# Driver.net
KiCad netlist of a schematic drawn in Altium Designer
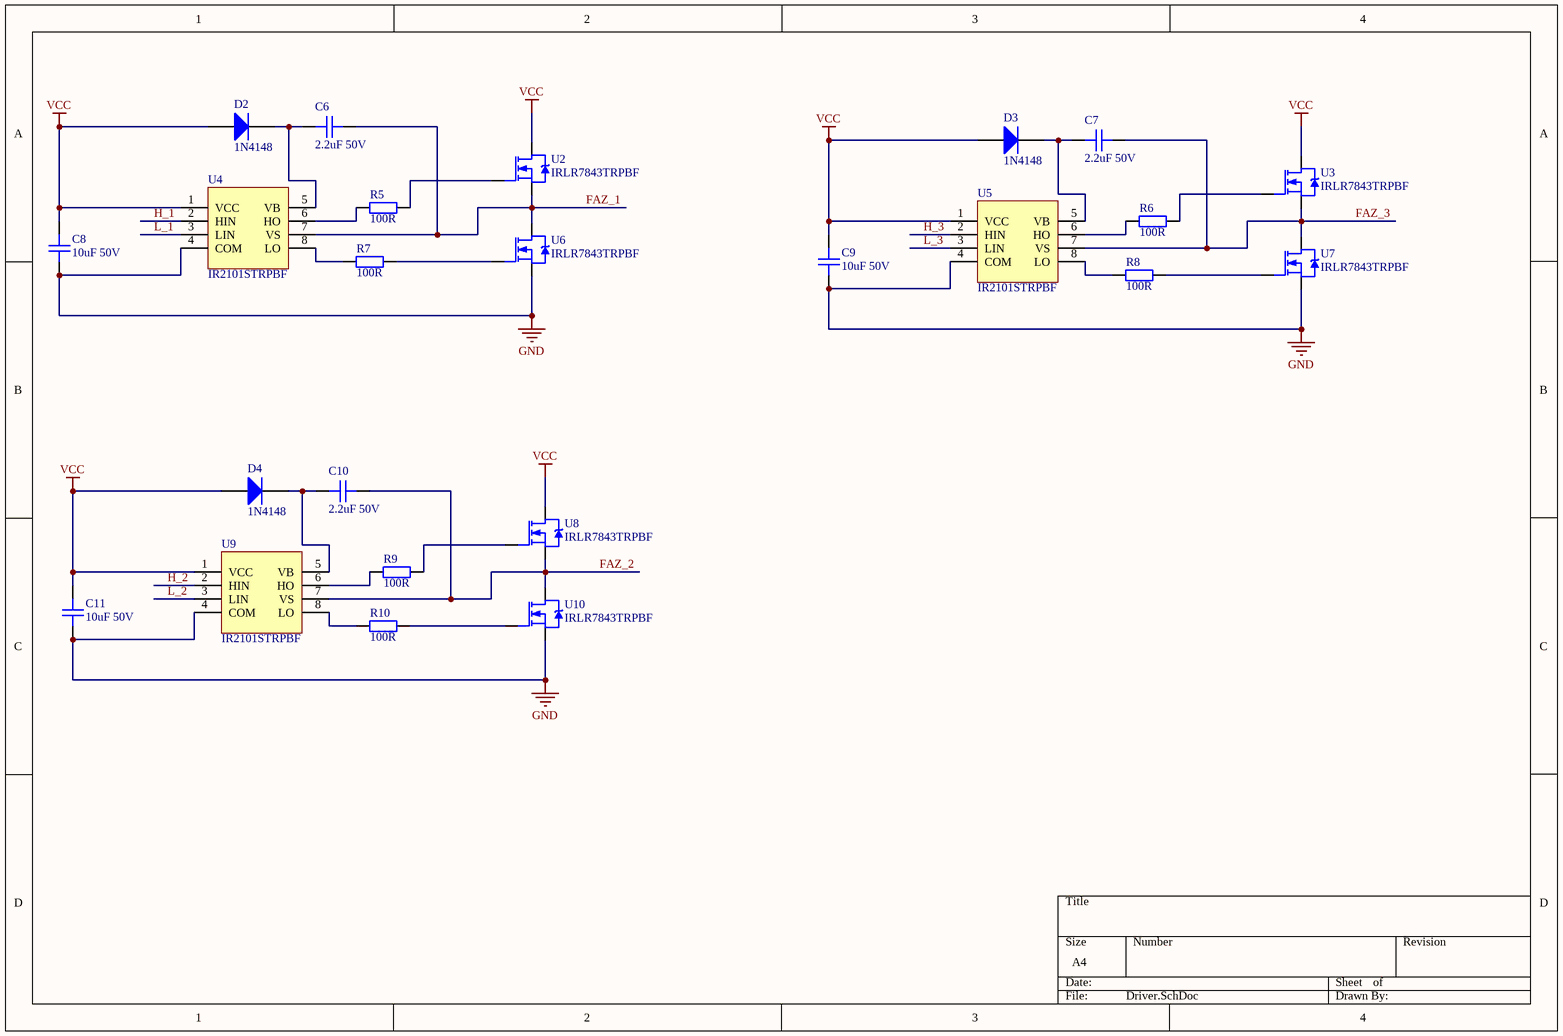
[diagram p0: Driver.SchDoc]

(export (version "E")
  (design (tool "Eeschema 10.0.6"))
  (components
    (comp (ref "C6")
      (value "CAP CER 2.2UF 50V X5R 1206")
      (footprint "CAP 1206/3216")
      (description "2.2µF ±10% 50V Ceramic Capacitor X5R 1206 (3216 Metric)")
      (fields (field (name "DEGER") "2.2uF 50V"))
      (libsource (lib "ESC") (part "2.2uF 50V 1206"))
    )
    (comp (ref "C7")
      (value "CAP CER 2.2UF 50V X5R 1206")
      (footprint "CAP 1206/3216")
      (description "2.2µF ±10% 50V Ceramic Capacitor X5R 1206 (3216 Metric)")
      (fields (field (name "DEGER") "2.2uF 50V"))
      (libsource (lib "ESC") (part "2.2uF 50V 1206"))
    )
    (comp (ref "C8")
      (value "CAP CER 10UF 50V X5R 1206")
      (footprint "CAP 1206/3216")
      (description "10µF ±10% 50V Ceramic Capacitor X5R 1206 (3216 Metric)")
      (fields (field (name "DEGER") "10uF 50V"))
      (libsource (lib "ESC") (part "10uF 50V 1206"))
    )
    (comp (ref "C9")
      (value "CAP CER 10UF 50V X5R 1206")
      (footprint "CAP 1206/3216")
      (description "10µF ±10% 50V Ceramic Capacitor X5R 1206 (3216 Metric)")
      (fields (field (name "DEGER") "10uF 50V"))
      (libsource (lib "ESC") (part "10uF 50V 1206"))
    )
    (comp (ref "C10")
      (value "CAP CER 2.2UF 50V X5R 1206")
      (footprint "CAP 1206/3216")
      (description "2.2µF ±10% 50V Ceramic Capacitor X5R 1206 (3216 Metric)")
      (fields (field (name "DEGER") "2.2uF 50V"))
      (libsource (lib "ESC") (part "2.2uF 50V 1206"))
    )
    (comp (ref "C11")
      (value "CAP CER 10UF 50V X5R 1206")
      (footprint "CAP 1206/3216")
      (description "10µF ±10% 50V Ceramic Capacitor X5R 1206 (3216 Metric)")
      (fields (field (name "DEGER") "10uF 50V"))
      (libsource (lib "ESC") (part "10uF 50V 1206"))
    )
    (comp (ref "D2")
      (value "1N4148 Diyot")
      (footprint "SOD-123")
      (description "DIODE GEN PURP 100V 150MA SOD123")
      (fields (field (name "DEGER") "1N4148"))
      (libsource (lib "ESC") (part "1N4148"))
    )
    (comp (ref "D3")
      (value "1N4148 Diyot")
      (footprint "SOD-123")
      (description "DIODE GEN PURP 100V 150MA SOD123")
      (fields (field (name "DEGER") "1N4148"))
      (libsource (lib "ESC") (part "1N4148"))
    )
    (comp (ref "D4")
      (value "1N4148 Diyot")
      (footprint "SOD-123")
      (description "DIODE GEN PURP 100V 150MA SOD123")
      (fields (field (name "DEGER") "1N4148"))
      (libsource (lib "ESC") (part "1N4148"))
    )
    (comp (ref "R5")
      (value "RES SMD 100 OHM 1% 1/8W 0805")
      (footprint "RES-0805")
      (description "100 Ohms ±1% 0.125W, 1/8W Chip Resistor 0805 (2012 Metric) Moisture Resistant Thick Film")
      (fields (field (name "DEGER") "100R"))
      (libsource (lib "ESC") (part "100R 0805"))
    )
    (comp (ref "R6")
      (value "RES SMD 100 OHM 1% 1/8W 0805")
      (footprint "RES-0805")
      (description "100 Ohms ±1% 0.125W, 1/8W Chip Resistor 0805 (2012 Metric) Moisture Resistant Thick Film")
      (fields (field (name "DEGER") "100R"))
      (libsource (lib "ESC") (part "100R 0805"))
    )
    (comp (ref "R7")
      (value "RES SMD 100 OHM 1% 1/8W 0805")
      (footprint "RES-0805")
      (description "100 Ohms ±1% 0.125W, 1/8W Chip Resistor 0805 (2012 Metric) Moisture Resistant Thick Film")
      (fields (field (name "DEGER") "100R"))
      (libsource (lib "ESC") (part "100R 0805"))
    )
    (comp (ref "R8")
      (value "RES SMD 100 OHM 1% 1/8W 0805")
      (footprint "RES-0805")
      (description "100 Ohms ±1% 0.125W, 1/8W Chip Resistor 0805 (2012 Metric) Moisture Resistant Thick Film")
      (fields (field (name "DEGER") "100R"))
      (libsource (lib "ESC") (part "100R 0805"))
    )
    (comp (ref "R9")
      (value "RES SMD 100 OHM 1% 1/8W 0805")
      (footprint "RES-0805")
      (description "100 Ohms ±1% 0.125W, 1/8W Chip Resistor 0805 (2012 Metric) Moisture Resistant Thick Film")
      (fields (field (name "DEGER") "100R"))
      (libsource (lib "ESC") (part "100R 0805"))
    )
    (comp (ref "R10")
      (value "RES SMD 100 OHM 1% 1/8W 0805")
      (footprint "RES-0805")
      (description "100 Ohms ±1% 0.125W, 1/8W Chip Resistor 0805 (2012 Metric) Moisture Resistant Thick Film")
      (fields (field (name "DEGER") "100R"))
      (libsource (lib "ESC") (part "100R 0805"))
    )
    (comp (ref "U2")
      (value "MOSFET N-CH 30V 161A DPAK")
      (footprint "DPAK")
      (description "N-Channel 30V 161A (Tc) 140W (Tc) Surface Mount D-Pak")
      (fields (field (name "DEGER") "IRLR7843TRPBF"))
      (libsource (lib "ESC_Project") (part "IRLR7843"))
    )
    (comp (ref "U3")
      (value "MOSFET N-CH 30V 161A DPAK")
      (footprint "DPAK")
      (description "N-Channel 30V 161A (Tc) 140W (Tc) Surface Mount D-Pak")
      (fields (field (name "DEGER") "IRLR7843TRPBF"))
      (libsource (lib "ESC_Project") (part "IRLR7843"))
    )
    (comp (ref "U4")
      (value "IC GATE DRVR HALF-BRIDGE 8SOIC")
      (footprint "SOIC8")
      (description "Half-Bridge Gate Driver IC Non-Inverting 8-SOIC")
      (fields (field (name "DEGER") "IR2101STRPBF"))
      (libsource (lib "ESC") (part "IR2101"))
    )
    (comp (ref "U5")
      (value "IC GATE DRVR HALF-BRIDGE 8SOIC")
      (footprint "SOIC8")
      (description "Half-Bridge Gate Driver IC Non-Inverting 8-SOIC")
      (fields (field (name "DEGER") "IR2101STRPBF"))
      (libsource (lib "ESC") (part "IR2101"))
    )
    (comp (ref "U6")
      (value "MOSFET N-CH 30V 161A DPAK")
      (footprint "DPAK")
      (description "N-Channel 30V 161A (Tc) 140W (Tc) Surface Mount D-Pak")
      (fields (field (name "DEGER") "IRLR7843TRPBF"))
      (libsource (lib "ESC_Project") (part "IRLR7843"))
    )
    (comp (ref "U7")
      (value "MOSFET N-CH 30V 161A DPAK")
      (footprint "DPAK")
      (description "N-Channel 30V 161A (Tc) 140W (Tc) Surface Mount D-Pak")
      (fields (field (name "DEGER") "IRLR7843TRPBF"))
      (libsource (lib "ESC_Project") (part "IRLR7843"))
    )
    (comp (ref "U8")
      (value "MOSFET N-CH 30V 161A DPAK")
      (footprint "DPAK")
      (description "N-Channel 30V 161A (Tc) 140W (Tc) Surface Mount D-Pak")
      (fields (field (name "DEGER") "IRLR7843TRPBF"))
      (libsource (lib "ESC_Project") (part "IRLR7843"))
    )
    (comp (ref "U9")
      (value "IC GATE DRVR HALF-BRIDGE 8SOIC")
      (footprint "SOIC8")
      (description "Half-Bridge Gate Driver IC Non-Inverting 8-SOIC")
      (fields (field (name "DEGER") "IR2101STRPBF"))
      (libsource (lib "ESC") (part "IR2101"))
    )
    (comp (ref "U10")
      (value "MOSFET N-CH 30V 161A DPAK")
      (footprint "DPAK")
      (description "N-Channel 30V 161A (Tc) 140W (Tc) Surface Mount D-Pak")
      (fields (field (name "DEGER") "IRLR7843TRPBF"))
      (libsource (lib "ESC_Project") (part "IRLR7843"))
    )
  )
  (nets
    (net (code "1") (name "/FAZ_1") (class "Default")
      (node (ref "C6") (pin "2") (pinfunction "2_2") (pintype "passive"))
      (node (ref "U2") (pin "3") (pinfunction "S_3") (pintype "passive"))
      (node (ref "U4") (pin "7") (pinfunction "VS_7") (pintype "passive"))
      (node (ref "U6") (pin "4") (pinfunction "D_4") (pintype "passive"))
    )
    (net (code "2") (name "/FAZ_2") (class "Default")
      (node (ref "C10") (pin "2") (pinfunction "2_2") (pintype "passive"))
      (node (ref "U10") (pin "4") (pinfunction "D_4") (pintype "passive"))
      (node (ref "U8") (pin "3") (pinfunction "S_3") (pintype "passive"))
      (node (ref "U9") (pin "7") (pinfunction "VS_7") (pintype "passive"))
    )
    (net (code "3") (name "/FAZ_3") (class "Default")
      (node (ref "C7") (pin "2") (pinfunction "2_2") (pintype "passive"))
      (node (ref "U3") (pin "3") (pinfunction "S_3") (pintype "passive"))
      (node (ref "U5") (pin "7") (pinfunction "VS_7") (pintype "passive"))
      (node (ref "U7") (pin "4") (pinfunction "D_4") (pintype "passive"))
    )
    (net (code "4") (name "/H_1") (class "Default")
      (node (ref "U4") (pin "2") (pinfunction "HIN_2") (pintype "passive"))
    )
    (net (code "5") (name "/H_2") (class "Default")
      (node (ref "U9") (pin "2") (pinfunction "HIN_2") (pintype "passive"))
    )
    (net (code "6") (name "/H_3") (class "Default")
      (node (ref "U5") (pin "2") (pinfunction "HIN_2") (pintype "passive"))
    )
    (net (code "7") (name "/L_1") (class "Default")
      (node (ref "U4") (pin "3") (pinfunction "LIN_3") (pintype "passive"))
    )
    (net (code "8") (name "/L_2") (class "Default")
      (node (ref "U9") (pin "3") (pinfunction "LIN_3") (pintype "passive"))
    )
    (net (code "9") (name "/L_3") (class "Default")
      (node (ref "U5") (pin "3") (pinfunction "LIN_3") (pintype "passive"))
    )
    (net (code "10") (name "GND") (class "Default")
      (node (ref "C11") (pin "1") (pinfunction "1_1") (pintype "passive"))
      (node (ref "C8") (pin "1") (pinfunction "1_1") (pintype "passive"))
      (node (ref "C9") (pin "1") (pinfunction "1_1") (pintype "passive"))
      (node (ref "U10") (pin "3") (pinfunction "S_3") (pintype "passive"))
      (node (ref "U4") (pin "4") (pinfunction "COM_4") (pintype "passive"))
      (node (ref "U5") (pin "4") (pinfunction "COM_4") (pintype "passive"))
      (node (ref "U6") (pin "3") (pinfunction "S_3") (pintype "passive"))
      (node (ref "U7") (pin "3") (pinfunction "S_3") (pintype "passive"))
      (node (ref "U9") (pin "4") (pinfunction "COM_4") (pintype "passive"))
    )
    (net (code "11") (name "Net-(D2-K)") (class "Default")
      (node (ref "C6") (pin "1") (pinfunction "1_1") (pintype "passive"))
      (node (ref "D2") (pin "2") (pinfunction "K_2") (pintype "passive"))
      (node (ref "U4") (pin "5") (pinfunction "VB_5") (pintype "passive"))
    )
    (net (code "12") (name "Net-(D3-K)") (class "Default")
      (node (ref "C7") (pin "1") (pinfunction "1_1") (pintype "passive"))
      (node (ref "D3") (pin "2") (pinfunction "K_2") (pintype "passive"))
      (node (ref "U5") (pin "5") (pinfunction "VB_5") (pintype "passive"))
    )
    (net (code "13") (name "Net-(D4-K)") (class "Default")
      (node (ref "C10") (pin "1") (pinfunction "1_1") (pintype "passive"))
      (node (ref "D4") (pin "2") (pinfunction "K_2") (pintype "passive"))
      (node (ref "U9") (pin "5") (pinfunction "VB_5") (pintype "passive"))
    )
    (net (code "14") (name "Net-(U2-G)") (class "Default")
      (node (ref "R5") (pin "2") (pinfunction "2_2") (pintype "passive"))
      (node (ref "U2") (pin "1") (pinfunction "G_1") (pintype "passive"))
    )
    (net (code "15") (name "Net-(U3-G)") (class "Default")
      (node (ref "R6") (pin "2") (pinfunction "2_2") (pintype "passive"))
      (node (ref "U3") (pin "1") (pinfunction "G_1") (pintype "passive"))
    )
    (net (code "16") (name "Net-(U4-HO)") (class "Default")
      (node (ref "R5") (pin "1") (pinfunction "1_1") (pintype "passive"))
      (node (ref "U4") (pin "6") (pinfunction "HO_6") (pintype "passive"))
    )
    (net (code "17") (name "Net-(U4-LO)") (class "Default")
      (node (ref "R7") (pin "1") (pinfunction "1_1") (pintype "passive"))
      (node (ref "U4") (pin "8") (pinfunction "LO_8") (pintype "passive"))
    )
    (net (code "18") (name "Net-(U5-HO)") (class "Default")
      (node (ref "R6") (pin "1") (pinfunction "1_1") (pintype "passive"))
      (node (ref "U5") (pin "6") (pinfunction "HO_6") (pintype "passive"))
    )
    (net (code "19") (name "Net-(U5-LO)") (class "Default")
      (node (ref "R8") (pin "1") (pinfunction "1_1") (pintype "passive"))
      (node (ref "U5") (pin "8") (pinfunction "LO_8") (pintype "passive"))
    )
    (net (code "20") (name "Net-(U6-G)") (class "Default")
      (node (ref "R7") (pin "2") (pinfunction "2_2") (pintype "passive"))
      (node (ref "U6") (pin "1") (pinfunction "G_1") (pintype "passive"))
    )
    (net (code "21") (name "Net-(U7-G)") (class "Default")
      (node (ref "R8") (pin "2") (pinfunction "2_2") (pintype "passive"))
      (node (ref "U7") (pin "1") (pinfunction "G_1") (pintype "passive"))
    )
    (net (code "22") (name "Net-(U8-G)") (class "Default")
      (node (ref "R9") (pin "2") (pinfunction "2_2") (pintype "passive"))
      (node (ref "U8") (pin "1") (pinfunction "G_1") (pintype "passive"))
    )
    (net (code "23") (name "Net-(U9-HO)") (class "Default")
      (node (ref "R9") (pin "1") (pinfunction "1_1") (pintype "passive"))
      (node (ref "U9") (pin "6") (pinfunction "HO_6") (pintype "passive"))
    )
    (net (code "24") (name "Net-(U9-LO)") (class "Default")
      (node (ref "R10") (pin "1") (pinfunction "1_1") (pintype "passive"))
      (node (ref "U9") (pin "8") (pinfunction "LO_8") (pintype "passive"))
    )
    (net (code "25") (name "Net-(U10-G)") (class "Default")
      (node (ref "R10") (pin "2") (pinfunction "2_2") (pintype "passive"))
      (node (ref "U10") (pin "1") (pinfunction "G_1") (pintype "passive"))
    )
    (net (code "26") (name "VCC") (class "Default")
      (node (ref "C11") (pin "2") (pinfunction "2_2") (pintype "passive"))
      (node (ref "C8") (pin "2") (pinfunction "2_2") (pintype "passive"))
      (node (ref "C9") (pin "2") (pinfunction "2_2") (pintype "passive"))
      (node (ref "D2") (pin "1") (pinfunction "A_1") (pintype "passive"))
      (node (ref "D3") (pin "1") (pinfunction "A_1") (pintype "passive"))
      (node (ref "D4") (pin "1") (pinfunction "A_1") (pintype "passive"))
      (node (ref "U2") (pin "4") (pinfunction "D_4") (pintype "passive"))
      (node (ref "U3") (pin "4") (pinfunction "D_4") (pintype "passive"))
      (node (ref "U4") (pin "1") (pinfunction "VCC_1") (pintype "passive"))
      (node (ref "U5") (pin "1") (pinfunction "VCC_1") (pintype "passive"))
      (node (ref "U8") (pin "4") (pinfunction "D_4") (pintype "passive"))
      (node (ref "U9") (pin "1") (pinfunction "VCC_1") (pintype "passive"))
    )
  )
)
